# FE3_V3_REV10c.net
KiCad netlist of a schematic drawn in EAGLE
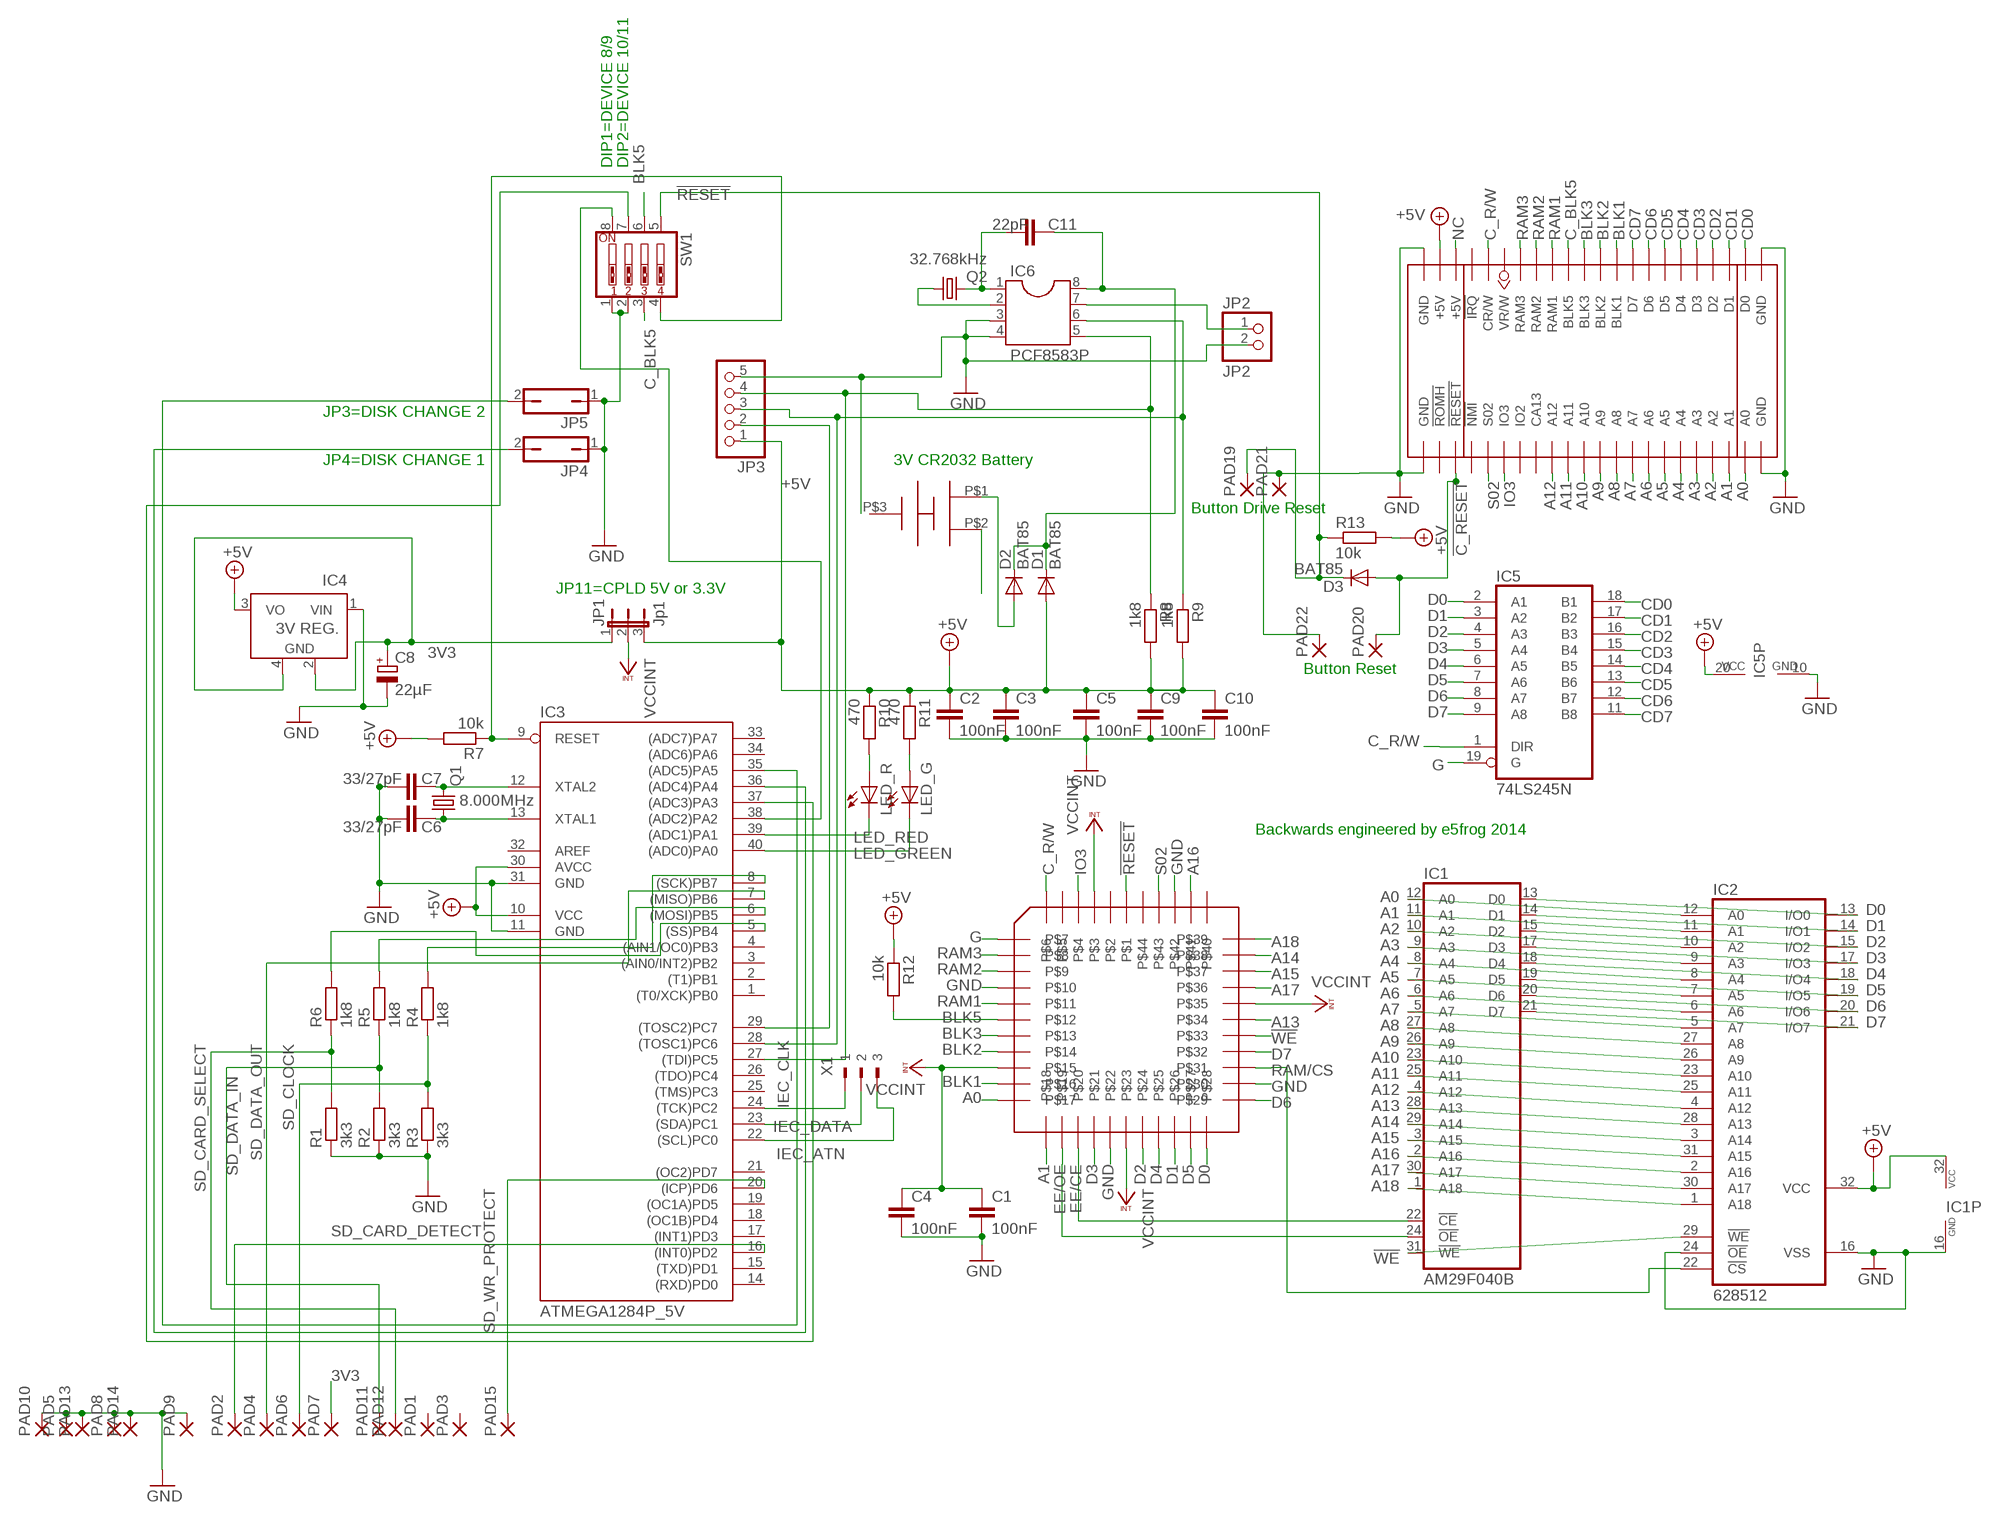
[diagram p0: schematic, sheet 1]

(export (version "E")
  (design (tool "Eeschema 10.0.6"))
  (components
    (comp (ref "C1")
      (value "100nF")
      (footprint "eagle-import:C050-025X075")
      (libsource (lib "eagle-import") (part "C-EU050-025X075"))
    )
    (comp (ref "C2")
      (value "100nF")
      (footprint "eagle-import:C050-025X075")
      (libsource (lib "eagle-import") (part "C-EU050-025X075"))
    )
    (comp (ref "C3")
      (value "100nF")
      (footprint "eagle-import:C050-025X075")
      (libsource (lib "eagle-import") (part "C-EU050-025X075"))
    )
    (comp (ref "C4")
      (value "100nF")
      (footprint "eagle-import:C050-025X075")
      (libsource (lib "eagle-import") (part "C-EU050-025X075"))
    )
    (comp (ref "C5")
      (value "100nF")
      (footprint "eagle-import:C050-025X075")
      (libsource (lib "eagle-import") (part "C-EU050-025X075"))
    )
    (comp (ref "C6")
      (value "33/27pF")
      (footprint "eagle-import:C025-024X044")
      (libsource (lib "eagle-import") (part "C-EU025-024X044"))
    )
    (comp (ref "C7")
      (value "33/27pF")
      (footprint "eagle-import:C025-024X044")
      (libsource (lib "eagle-import") (part "C-EU025-024X044"))
    )
    (comp (ref "C8")
      (value "22µF")
      (footprint "eagle-import:E2-4")
      (libsource (lib "eagle-import") (part "CPOL-EUE2-4"))
    )
    (comp (ref "C9")
      (value "100nF")
      (footprint "eagle-import:C050-025X075")
      (libsource (lib "eagle-import") (part "C-EU050-025X075"))
    )
    (comp (ref "C10")
      (value "100nF")
      (footprint "eagle-import:C050-025X075")
      (libsource (lib "eagle-import") (part "C-EU050-025X075"))
    )
    (comp (ref "C11")
      (value "22pF")
      (footprint "eagle-import:C5B2.5")
      (libsource (lib "eagle-import") (part "C5/2.5"))
    )
    (comp (ref "D1")
      (value "BAT85")
      (footprint "eagle-import:DO34-7")
      (libsource (lib "eagle-import") (part "BAT81"))
    )
    (comp (ref "D2")
      (value "BAT85")
      (footprint "eagle-import:DO34-7")
      (libsource (lib "eagle-import") (part "BAT81"))
    )
    (comp (ref "D3")
      (value "BAT85")
      (footprint "eagle-import:DO34-7")
      (libsource (lib "eagle-import") (part "BAT81"))
    )
    (comp (ref "IC1")
      (value "AM29F040B")
      (footprint "eagle-import:DIL32")
      (libsource (lib "eagle-import") (part "AM29F040PAM29F040B"))
    )
    (comp (ref "IC2")
      (value "628512")
      (footprint "eagle-import:DIL32")
      (libsource (lib "eagle-import") (part "628512P"))
    )
    (comp (ref "IC3")
      (value "ATMEGA1284P_5V")
      (footprint "eagle-import:DIL40")
      (fields (field (name "MPN") "ATMEGA32-16PU"))
      (libsource (lib "eagle-import") (part "MEGA32-P"))
    )
    (comp (ref "IC4")
      (value "3V REG.")
      (footprint "eagle-import:SOT223")
      (fields (field (name "MF") "NATIONAL SEMICONDUCTOR") (field (name "MPN") "LM2936MP-3.0/NOPB"))
      (libsource (lib "eagle-import") (part "LM2936MP?-3.0"))
    )
    (comp (ref "IC5")
      (value "74LS245N")
      (footprint "eagle-import:DIL20")
      (libsource (lib "eagle-import") (part "74245NLS"))
    )
    (comp (ref "IC6")
      (value "PCF8583P")
      (footprint "eagle-import:DIL08")
      (libsource (lib "eagle-import") (part "DIL8"))
    )
    (comp (ref "JP1")
      (value "Jp1")
      (footprint "eagle-import:JP2_N")
      (libsource (lib "eagle-import") (part "JP2E_N"))
    )
    (comp (ref "JP2")
      (value "JP2")
      (footprint "eagle-import:1X02")
      (libsource (lib "eagle-import") (part "PINHD-1X2"))
    )
    (comp (ref "JP3")
      (value "PINHD-1X5")
      (footprint "eagle-import:1X05")
      (libsource (lib "eagle-import") (part "PINHD-1X5"))
    )
    (comp (ref "JP4")
      (value "JP1Q")
      (footprint "eagle-import:JP1")
      (libsource (lib "eagle-import") (part "JP1Q"))
    )
    (comp (ref "JP5")
      (value "JP1Q")
      (footprint "eagle-import:JP1")
      (libsource (lib "eagle-import") (part "JP1Q"))
    )
    (comp (ref "LED_G")
      (value "LED3MM")
      (footprint "eagle-import:LED3MM")
      (libsource (lib "eagle-import") (part "LED3MM"))
    )
    (comp (ref "LED_R")
      (value "LED3MM")
      (footprint "eagle-import:LED3MM")
      (libsource (lib "eagle-import") (part "LED3MM"))
    )
    (comp (ref "PAD1")
      (value "SMD_EZ1")
      (footprint "eagle-import:SMD0,7-254")
      (libsource (lib "eagle-import") (part "SMD_EZ1"))
    )
    (comp (ref "PAD2")
      (value "SMD_EZ1")
      (footprint "eagle-import:SMD0,7-254")
      (libsource (lib "eagle-import") (part "SMD_EZ1"))
    )
    (comp (ref "PAD3")
      (value "SMD2")
      (footprint "eagle-import:SMD1,27-2,54")
      (libsource (lib "eagle-import") (part "SMD2"))
    )
    (comp (ref "PAD4")
      (value "SMD2")
      (footprint "eagle-import:SMD1,27-2,54")
      (libsource (lib "eagle-import") (part "SMD2"))
    )
    (comp (ref "PAD5")
      (value "SMD2")
      (footprint "eagle-import:SMD1,27-2,54")
      (libsource (lib "eagle-import") (part "SMD2"))
    )
    (comp (ref "PAD6")
      (value "SMD2")
      (footprint "eagle-import:SMD1,27-2,54")
      (libsource (lib "eagle-import") (part "SMD2"))
    )
    (comp (ref "PAD7")
      (value "SMD2")
      (footprint "eagle-import:SMD1,27-2,54")
      (libsource (lib "eagle-import") (part "SMD2"))
    )
    (comp (ref "PAD8")
      (value "SMD2")
      (footprint "eagle-import:SMD1,27-2,54")
      (libsource (lib "eagle-import") (part "SMD2"))
    )
    (comp (ref "PAD9")
      (value "SMD2")
      (footprint "eagle-import:SMD1,27-2,54")
      (libsource (lib "eagle-import") (part "SMD2"))
    )
    (comp (ref "PAD10")
      (value "SMD2")
      (footprint "eagle-import:SMD1,27-2,54")
      (libsource (lib "eagle-import") (part "SMD2"))
    )
    (comp (ref "PAD11")
      (value "SMD2")
      (footprint "eagle-import:SMD1,27-2,54")
      (libsource (lib "eagle-import") (part "SMD2"))
    )
    (comp (ref "PAD12")
      (value "SMD2")
      (footprint "eagle-import:SMD1,27-2,54")
      (libsource (lib "eagle-import") (part "SMD2"))
    )
    (comp (ref "PAD13")
      (value "SMD2")
      (footprint "eagle-import:SMD1,27-2,54")
      (libsource (lib "eagle-import") (part "SMD2"))
    )
    (comp (ref "PAD14")
      (value "SMD2")
      (footprint "eagle-import:SMD1,27-2,54")
      (libsource (lib "eagle-import") (part "SMD2"))
    )
    (comp (ref "PAD15")
      (value "SMD_EZ1")
      (footprint "eagle-import:SMD0,7-254")
      (libsource (lib "eagle-import") (part "SMD_EZ1"))
    )
    (comp (ref "PAD19")
      (value "SMD5")
      (footprint "eagle-import:SMD2,54-5,08")
      (libsource (lib "eagle-import") (part "SMD5"))
    )
    (comp (ref "PAD20")
      (value "SMD5")
      (footprint "eagle-import:SMD2,54-5,08")
      (libsource (lib "eagle-import") (part "SMD5"))
    )
    (comp (ref "PAD21")
      (value "SMD5")
      (footprint "eagle-import:SMD2,54-5,08")
      (libsource (lib "eagle-import") (part "SMD5"))
    )
    (comp (ref "PAD22")
      (value "SMD5")
      (footprint "eagle-import:SMD2,54-5,08")
      (libsource (lib "eagle-import") (part "SMD5"))
    )
    (comp (ref "Q1")
      (value "8.000MHz")
      (footprint "eagle-import:HC49U-V")
      (libsource (lib "eagle-import") (part "CRYSTALHC49U-V"))
    )
    (comp (ref "Q2")
      (value "32.768kHz")
      (footprint "eagle-import:TC26H")
      (libsource (lib "eagle-import") (part "CRYSTALTC26H"))
    )
    (comp (ref "R1")
      (value "3k3")
      (footprint "eagle-import:0207_10")
      (libsource (lib "eagle-import") (part "R-EU_0207/10"))
    )
    (comp (ref "R2")
      (value "3k3")
      (footprint "eagle-import:0207_10")
      (libsource (lib "eagle-import") (part "R-EU_0207/10"))
    )
    (comp (ref "R3")
      (value "3k3")
      (footprint "eagle-import:0207_10")
      (libsource (lib "eagle-import") (part "R-EU_0207/10"))
    )
    (comp (ref "R4")
      (value "1k8")
      (footprint "eagle-import:0207_10")
      (libsource (lib "eagle-import") (part "R-EU_0207/10"))
    )
    (comp (ref "R5")
      (value "1k8")
      (footprint "eagle-import:0207_10")
      (libsource (lib "eagle-import") (part "R-EU_0207/10"))
    )
    (comp (ref "R6")
      (value "1k8")
      (footprint "eagle-import:0207_10")
      (libsource (lib "eagle-import") (part "R-EU_0207/10"))
    )
    (comp (ref "R7")
      (value "10k")
      (footprint "eagle-import:0207_10")
      (libsource (lib "eagle-import") (part "R-EU_0207/10"))
    )
    (comp (ref "R8")
      (value "1k8")
      (footprint "eagle-import:0207_10")
      (libsource (lib "eagle-import") (part "R-EU_0207/10"))
    )
    (comp (ref "R9")
      (value "1k8")
      (footprint "eagle-import:0207_10")
      (libsource (lib "eagle-import") (part "R-EU_0207/10"))
    )
    (comp (ref "R10")
      (value "470")
      (footprint "eagle-import:0207_10")
      (libsource (lib "eagle-import") (part "R-EU_0207/10"))
    )
    (comp (ref "R11")
      (value "470")
      (footprint "eagle-import:0207_10")
      (libsource (lib "eagle-import") (part "R-EU_0207/10"))
    )
    (comp (ref "R12")
      (value "10k")
      (footprint "eagle-import:0207_10")
      (libsource (lib "eagle-import") (part "R-EU_0207/10"))
    )
    (comp (ref "R13")
      (value "10k")
      (footprint "eagle-import:0207_10")
      (libsource (lib "eagle-import") (part "R-EU_0207/10"))
    )
    (comp (ref "SW1")
      (value "SW_DIP-4")
      (footprint "eagle-import:EDG-04")
      (libsource (lib "eagle-import") (part "SW_DIP-4"))
    )
    (comp (ref "U$1")
      (value "CPLD-ATF1504-AS")
      (footprint "eagle-import:S44")
      (libsource (lib "eagle-import") (part "CPLD-ATF1504-AS"))
    )
    (comp (ref "U$2")
      (value "VIC-20_EXPANSION")
      (footprint "eagle-import:VIC-20_EXPANSION")
      (libsource (lib "eagle-import") (part "VIC-20_EXPANSION"))
    )
    (comp (ref "U$3")
      (value "CR2032_RETAINER_PK5")
      (footprint "eagle-import:CR2032_RETAINER_PK5")
      (libsource (lib "eagle-import") (part "CR2032_RETAINER_PK5"))
    )
    (comp (ref "X1")
      (value "90-3")
      (footprint "eagle-import:90-3")
      (libsource (lib "eagle-import") (part "90-3"))
    )
  )
  (nets
    (net (code "1") (name "+5V") (class "Default")
      (node (ref "C10") (pin "1") (pinfunction "1_1") (pintype "passive"))
      (node (ref "C2") (pin "1") (pinfunction "1_1") (pintype "passive"))
      (node (ref "C3") (pin "1") (pinfunction "1_1") (pintype "passive"))
      (node (ref "C5") (pin "1") (pinfunction "1_1") (pintype "passive"))
      (node (ref "C9") (pin "1") (pinfunction "1_1") (pintype "passive"))
      (node (ref "D1") (pin "A") (pinfunction "A_A") (pintype "passive"))
      (node (ref "IC1") (pin "32") (pinfunction "VCC_32") (pintype "power_in"))
      (node (ref "IC2") (pin "32") (pinfunction "VCC_32") (pintype "power_in"))
      (node (ref "IC3") (pin "10") (pinfunction "VCC_10") (pintype "power_in"))
      (node (ref "IC3") (pin "30") (pinfunction "AVCC_30") (pintype "power_in"))
      (node (ref "IC4") (pin "3") (pinfunction "VO_3") (pintype "passive"))
      (node (ref "IC5") (pin "20") (pinfunction "VCC_20") (pintype "power_in"))
      (node (ref "JP1") (pin "3") (pinfunction "3_3") (pintype "passive"))
      (node (ref "JP3") (pin "1") (pinfunction "1_1") (pintype "passive"))
      (node (ref "R10") (pin "1") (pinfunction "1_1") (pintype "passive"))
      (node (ref "R11") (pin "1") (pinfunction "1_1") (pintype "passive"))
      (node (ref "R12") (pin "1") (pinfunction "1_1") (pintype "passive"))
      (node (ref "R13") (pin "2") (pinfunction "2_2") (pintype "passive"))
      (node (ref "R7") (pin "2") (pinfunction "2_2") (pintype "passive"))
      (node (ref "R8") (pin "2") (pinfunction "2_2") (pintype "passive"))
      (node (ref "R9") (pin "2") (pinfunction "2_2") (pintype "passive"))
      (node (ref "U$2") (pin "P$2") (pinfunction "+5V_P$2") (pintype "power_in"))
    )
    (net (code "2") (name "/3V3") (class "Default")
      (node (ref "C8") (pin "+") (pinfunction "+_+") (pintype "passive"))
      (node (ref "IC4") (pin "2") (pinfunction "GND_2") (pintype "passive"))
      (node (ref "IC4") (pin "4") (pinfunction "GND_4") (pintype "passive"))
      (node (ref "JP1") (pin "1") (pinfunction "1_1") (pintype "passive"))
      (node (ref "PAD7") (pin "1") (pinfunction "P_1") (pintype "passive"))
    )
    (net (code "3") (name "/A0") (class "Default")
      (node (ref "IC1") (pin "12") (pinfunction "A0_12") (pintype "input"))
      (node (ref "IC2") (pin "12") (pinfunction "A0_12") (pintype "input"))
      (node (ref "U$1") (pin "17") (pinfunction "P$17_17") (pintype "bidirectional"))
      (node (ref "U$2") (pin "P$43") (pinfunction "A0_P$43") (pintype "bidirectional"))
    )
    (net (code "4") (name "/A1") (class "Default")
      (node (ref "IC1") (pin "11") (pinfunction "A1_11") (pintype "input"))
      (node (ref "IC2") (pin "11") (pinfunction "A1_11") (pintype "input"))
      (node (ref "U$1") (pin "18") (pinfunction "P$18_18") (pintype "bidirectional"))
      (node (ref "U$2") (pin "P$42") (pinfunction "A1_P$42") (pintype "bidirectional"))
    )
    (net (code "5") (name "/A2") (class "Default")
      (node (ref "IC1") (pin "10") (pinfunction "A2_10") (pintype "input"))
      (node (ref "IC2") (pin "10") (pinfunction "A2_10") (pintype "input"))
      (node (ref "U$2") (pin "P$41") (pinfunction "A2_P$41") (pintype "bidirectional"))
    )
    (net (code "6") (name "/A3") (class "Default")
      (node (ref "IC1") (pin "9") (pinfunction "A3_9") (pintype "input"))
      (node (ref "IC2") (pin "9") (pinfunction "A3_9") (pintype "input"))
      (node (ref "U$2") (pin "P$40") (pinfunction "A3_P$40") (pintype "bidirectional"))
    )
    (net (code "7") (name "/A4") (class "Default")
      (node (ref "IC1") (pin "8") (pinfunction "A4_8") (pintype "input"))
      (node (ref "IC2") (pin "8") (pinfunction "A4_8") (pintype "input"))
      (node (ref "U$2") (pin "P$39") (pinfunction "A4_P$39") (pintype "bidirectional"))
    )
    (net (code "8") (name "/A5") (class "Default")
      (node (ref "IC1") (pin "7") (pinfunction "A5_7") (pintype "input"))
      (node (ref "IC2") (pin "7") (pinfunction "A5_7") (pintype "input"))
      (node (ref "U$2") (pin "P$38") (pinfunction "A5_P$38") (pintype "bidirectional"))
    )
    (net (code "9") (name "/A6") (class "Default")
      (node (ref "IC1") (pin "6") (pinfunction "A6_6") (pintype "input"))
      (node (ref "IC2") (pin "6") (pinfunction "A6_6") (pintype "input"))
      (node (ref "U$2") (pin "P$37") (pinfunction "A6_P$37") (pintype "bidirectional"))
    )
    (net (code "10") (name "/A7") (class "Default")
      (node (ref "IC1") (pin "5") (pinfunction "A7_5") (pintype "input"))
      (node (ref "IC2") (pin "5") (pinfunction "A7_5") (pintype "input"))
      (node (ref "U$2") (pin "P$36") (pinfunction "A7_P$36") (pintype "bidirectional"))
    )
    (net (code "11") (name "/A8") (class "Default")
      (node (ref "IC1") (pin "27") (pinfunction "A8_27") (pintype "input"))
      (node (ref "IC2") (pin "27") (pinfunction "A8_27") (pintype "input"))
      (node (ref "U$2") (pin "P$35") (pinfunction "A8_P$35") (pintype "bidirectional"))
    )
    (net (code "12") (name "/A9") (class "Default")
      (node (ref "IC1") (pin "26") (pinfunction "A9_26") (pintype "input"))
      (node (ref "IC2") (pin "26") (pinfunction "A9_26") (pintype "input"))
      (node (ref "U$2") (pin "P$34") (pinfunction "A9_P$34") (pintype "bidirectional"))
    )
    (net (code "13") (name "/A10") (class "Default")
      (node (ref "IC1") (pin "23") (pinfunction "A10_23") (pintype "input"))
      (node (ref "IC2") (pin "23") (pinfunction "A10_23") (pintype "input"))
      (node (ref "U$2") (pin "P$33") (pinfunction "A10_P$33") (pintype "bidirectional"))
    )
    (net (code "14") (name "/A11") (class "Default")
      (node (ref "IC1") (pin "25") (pinfunction "A11_25") (pintype "input"))
      (node (ref "IC2") (pin "25") (pinfunction "A11_25") (pintype "input"))
      (node (ref "U$2") (pin "P$32") (pinfunction "A11_P$32") (pintype "bidirectional"))
    )
    (net (code "15") (name "/A12") (class "Default")
      (node (ref "IC1") (pin "4") (pinfunction "A12_4") (pintype "input"))
      (node (ref "IC2") (pin "4") (pinfunction "A12_4") (pintype "input"))
      (node (ref "U$2") (pin "P$31") (pinfunction "A12_P$31") (pintype "bidirectional"))
    )
    (net (code "16") (name "/A13") (class "Default")
      (node (ref "IC1") (pin "28") (pinfunction "A13_28") (pintype "input"))
      (node (ref "IC2") (pin "28") (pinfunction "A13_28") (pintype "input"))
      (node (ref "U$1") (pin "34") (pinfunction "P$34_34") (pintype "bidirectional"))
    )
    (net (code "17") (name "/A14") (class "Default")
      (node (ref "IC1") (pin "29") (pinfunction "A14_29") (pintype "input"))
      (node (ref "IC2") (pin "3") (pinfunction "A14_3") (pintype "input"))
      (node (ref "U$1") (pin "38") (pinfunction "P$38_38") (pintype "bidirectional"))
    )
    (net (code "18") (name "/A15") (class "Default")
      (node (ref "IC1") (pin "3") (pinfunction "A15_3") (pintype "input"))
      (node (ref "IC2") (pin "31") (pinfunction "A15_31") (pintype "input"))
      (node (ref "U$1") (pin "37") (pinfunction "P$37_37") (pintype "bidirectional"))
    )
    (net (code "19") (name "/A16") (class "Default")
      (node (ref "IC1") (pin "2") (pinfunction "A16_2") (pintype "input"))
      (node (ref "IC2") (pin "2") (pinfunction "A16_2") (pintype "input"))
      (node (ref "U$1") (pin "41") (pinfunction "P$41_41") (pintype "bidirectional"))
    )
    (net (code "20") (name "/A17") (class "Default")
      (node (ref "IC1") (pin "30") (pinfunction "A17_30") (pintype "input"))
      (node (ref "IC2") (pin "30") (pinfunction "A17_30") (pintype "input"))
      (node (ref "U$1") (pin "36") (pinfunction "P$36_36") (pintype "bidirectional"))
    )
    (net (code "21") (name "/A18") (class "Default")
      (node (ref "IC1") (pin "1") (pinfunction "A18_1") (pintype "input"))
      (node (ref "IC2") (pin "1") (pinfunction "A18_1") (pintype "input"))
      (node (ref "U$1") (pin "39") (pinfunction "P$39_39") (pintype "bidirectional"))
    )
    (net (code "22") (name "/BLK1") (class "Default")
      (node (ref "U$1") (pin "16") (pinfunction "P$16_16") (pintype "bidirectional"))
      (node (ref "U$2") (pin "P$13") (pinfunction "BLK1_P$13") (pintype "bidirectional"))
    )
    (net (code "23") (name "/BLK2") (class "Default")
      (node (ref "U$1") (pin "14") (pinfunction "P$14_14") (pintype "bidirectional"))
      (node (ref "U$2") (pin "P$12") (pinfunction "BLK2_P$12") (pintype "bidirectional"))
    )
    (net (code "24") (name "/BLK3") (class "Default")
      (node (ref "U$1") (pin "13") (pinfunction "P$13_13") (pintype "bidirectional"))
      (node (ref "U$2") (pin "P$11") (pinfunction "BLK3_P$11") (pintype "bidirectional"))
    )
    (net (code "25") (name "/BLK5") (class "Default")
      (node (ref "R12") (pin "2") (pinfunction "2_2") (pintype "passive"))
      (node (ref "SW1") (pin "6") (pinfunction "6_6") (pintype "passive"))
      (node (ref "U$1") (pin "12") (pinfunction "P$12_12") (pintype "bidirectional"))
    )
    (net (code "26") (name "/CD0") (class "Default")
      (node (ref "IC5") (pin "18") (pinfunction "B1_18") (pintype "bidirectional"))
      (node (ref "U$2") (pin "P$21") (pinfunction "D0_P$21") (pintype "bidirectional"))
    )
    (net (code "27") (name "/CD1") (class "Default")
      (node (ref "IC5") (pin "17") (pinfunction "B2_17") (pintype "bidirectional"))
      (node (ref "U$2") (pin "P$20") (pinfunction "D1_P$20") (pintype "bidirectional"))
    )
    (net (code "28") (name "/CD2") (class "Default")
      (node (ref "IC5") (pin "16") (pinfunction "B3_16") (pintype "bidirectional"))
      (node (ref "U$2") (pin "P$19") (pinfunction "D2_P$19") (pintype "bidirectional"))
    )
    (net (code "29") (name "/CD3") (class "Default")
      (node (ref "IC5") (pin "15") (pinfunction "B4_15") (pintype "bidirectional"))
      (node (ref "U$2") (pin "P$18") (pinfunction "D3_P$18") (pintype "bidirectional"))
    )
    (net (code "30") (name "/CD4") (class "Default")
      (node (ref "IC5") (pin "14") (pinfunction "B5_14") (pintype "bidirectional"))
      (node (ref "U$2") (pin "P$17") (pinfunction "D4_P$17") (pintype "bidirectional"))
    )
    (net (code "31") (name "/CD5") (class "Default")
      (node (ref "IC5") (pin "13") (pinfunction "B6_13") (pintype "bidirectional"))
      (node (ref "U$2") (pin "P$16") (pinfunction "D5_P$16") (pintype "bidirectional"))
    )
    (net (code "32") (name "/CD6") (class "Default")
      (node (ref "IC5") (pin "12") (pinfunction "B7_12") (pintype "bidirectional"))
      (node (ref "U$2") (pin "P$15") (pinfunction "D6_P$15") (pintype "bidirectional"))
    )
    (net (code "33") (name "/CD7") (class "Default")
      (node (ref "IC5") (pin "11") (pinfunction "B8_11") (pintype "bidirectional"))
      (node (ref "U$2") (pin "P$14") (pinfunction "D7_P$14") (pintype "bidirectional"))
    )
    (net (code "34") (name "/C_BLK5") (class "Default")
      (node (ref "SW1") (pin "3") (pinfunction "3_3") (pintype "passive"))
      (node (ref "U$2") (pin "P$10") (pinfunction "BLK5_P$10") (pintype "bidirectional"))
    )
    (net (code "35") (name "/C_R{slash}W") (class "Default")
      (node (ref "IC5") (pin "1") (pinfunction "DIR_1") (pintype "input"))
      (node (ref "U$1") (pin "6") (pinfunction "P$6_6") (pintype "bidirectional"))
      (node (ref "U$2") (pin "P$5") (pinfunction "CR/W_P$5") (pintype "bidirectional"))
    )
    (net (code "36") (name "/D0") (class "Default")
      (node (ref "IC1") (pin "13") (pinfunction "D0_13") (pintype "tri_state"))
      (node (ref "IC2") (pin "13") (pinfunction "I/O0_13") (pintype "bidirectional"))
      (node (ref "IC5") (pin "2") (pinfunction "A1_2") (pintype "bidirectional"))
      (node (ref "U$1") (pin "28") (pinfunction "P$28_28") (pintype "bidirectional"))
    )
    (net (code "37") (name "/D1") (class "Default")
      (node (ref "IC1") (pin "14") (pinfunction "D1_14") (pintype "tri_state"))
      (node (ref "IC2") (pin "14") (pinfunction "I/O1_14") (pintype "bidirectional"))
      (node (ref "IC5") (pin "3") (pinfunction "A2_3") (pintype "bidirectional"))
      (node (ref "U$1") (pin "26") (pinfunction "P$26_26") (pintype "bidirectional"))
    )
    (net (code "38") (name "/D2") (class "Default")
      (node (ref "IC1") (pin "15") (pinfunction "D2_15") (pintype "tri_state"))
      (node (ref "IC2") (pin "15") (pinfunction "I/O2_15") (pintype "bidirectional"))
      (node (ref "IC5") (pin "4") (pinfunction "A3_4") (pintype "bidirectional"))
      (node (ref "U$1") (pin "24") (pinfunction "P$24_24") (pintype "bidirectional"))
    )
    (net (code "39") (name "/D3") (class "Default")
      (node (ref "IC1") (pin "17") (pinfunction "D3_17") (pintype "tri_state"))
      (node (ref "IC2") (pin "17") (pinfunction "I/O3_17") (pintype "bidirectional"))
      (node (ref "IC5") (pin "5") (pinfunction "A4_5") (pintype "bidirectional"))
      (node (ref "U$1") (pin "21") (pinfunction "P$21_21") (pintype "bidirectional"))
    )
    (net (code "40") (name "/D4") (class "Default")
      (node (ref "IC1") (pin "18") (pinfunction "D4_18") (pintype "tri_state"))
      (node (ref "IC2") (pin "18") (pinfunction "I/O4_18") (pintype "bidirectional"))
      (node (ref "IC5") (pin "6") (pinfunction "A5_6") (pintype "bidirectional"))
      (node (ref "U$1") (pin "25") (pinfunction "P$25_25") (pintype "bidirectional"))
    )
    (net (code "41") (name "/D5") (class "Default")
      (node (ref "IC1") (pin "19") (pinfunction "D5_19") (pintype "tri_state"))
      (node (ref "IC2") (pin "19") (pinfunction "I/O5_19") (pintype "bidirectional"))
      (node (ref "IC5") (pin "7") (pinfunction "A6_7") (pintype "bidirectional"))
      (node (ref "U$1") (pin "27") (pinfunction "P$27_27") (pintype "bidirectional"))
    )
    (net (code "42") (name "/D6") (class "Default")
      (node (ref "IC1") (pin "20") (pinfunction "D6_20") (pintype "tri_state"))
      (node (ref "IC2") (pin "20") (pinfunction "I/O6_20") (pintype "bidirectional"))
      (node (ref "IC5") (pin "8") (pinfunction "A7_8") (pintype "bidirectional"))
      (node (ref "U$1") (pin "29") (pinfunction "P$29_29") (pintype "bidirectional"))
    )
    (net (code "43") (name "/D7") (class "Default")
      (node (ref "IC1") (pin "21") (pinfunction "D7_21") (pintype "tri_state"))
      (node (ref "IC2") (pin "21") (pinfunction "I/O7_21") (pintype "bidirectional"))
      (node (ref "IC5") (pin "9") (pinfunction "A8_9") (pintype "bidirectional"))
      (node (ref "U$1") (pin "32") (pinfunction "P$32_32") (pintype "bidirectional"))
    )
    (net (code "44") (name "/EE{slash}CE") (class "Default")
      (node (ref "IC1") (pin "22") (pinfunction "~{CE}_22") (pintype "input"))
      (node (ref "U$1") (pin "20") (pinfunction "P$20_20") (pintype "bidirectional"))
    )
    (net (code "45") (name "/EE{slash}OE") (class "Default")
      (node (ref "IC1") (pin "24") (pinfunction "~{OE}_24") (pintype "input"))
      (node (ref "U$1") (pin "19") (pinfunction "P$19_19") (pintype "bidirectional"))
    )
    (net (code "46") (name "/G") (class "Default")
      (node (ref "IC5") (pin "19") (pinfunction "G_19") (pintype "input"))
      (node (ref "U$1") (pin "7") (pinfunction "P$7_7") (pintype "bidirectional"))
    )
    (net (code "47") (name "/IEC_ATN") (class "Default")
      (node (ref "IC3") (pin "22") (pinfunction "(SCL)PC0_22") (pintype "bidirectional"))
      (node (ref "X1") (pin "3") (pinfunction "3_3") (pintype "passive"))
    )
    (net (code "48") (name "/IEC_CLK") (class "Default")
      (node (ref "IC3") (pin "24") (pinfunction "(TCK)PC2_24") (pintype "bidirectional"))
      (node (ref "X1") (pin "1") (pinfunction "1_1") (pintype "passive"))
    )
    (net (code "49") (name "/IEC_DATA") (class "Default")
      (node (ref "IC3") (pin "23") (pinfunction "(SDA)PC1_23") (pintype "bidirectional"))
      (node (ref "X1") (pin "2") (pinfunction "2_2") (pintype "passive"))
    )
    (net (code "50") (name "/IO3") (class "Default")
      (node (ref "U$1") (pin "4") (pinfunction "P$4_4") (pintype "bidirectional"))
      (node (ref "U$2") (pin "P$28") (pinfunction "IO3_P$28") (pintype "bidirectional"))
    )
    (net (code "51") (name "/LED_GREEN") (class "Default")
      (node (ref "IC3") (pin "40") (pinfunction "(ADC0)PA0_40") (pintype "bidirectional"))
      (node (ref "LED_G") (pin "K") (pinfunction "C_K") (pintype "passive"))
    )
    (net (code "52") (name "/LED_RED") (class "Default")
      (node (ref "IC3") (pin "39") (pinfunction "(ADC1)PA1_39") (pintype "bidirectional"))
      (node (ref "LED_R") (pin "K") (pinfunction "C_K") (pintype "passive"))
    )
    (net (code "53") (name "/NC") (class "Default")
      (node (ref "U$2") (pin "P$3") (pinfunction "+5V_P$3") (pintype "power_in"))
    )
    (net (code "54") (name "/P$3") (class "Default")
      (node (ref "U$3") (pin "P$3") (pinfunction "P$3_P$3") (pintype "power_in"))
    )
    (net (code "55") (name "/RAM1") (class "Default")
      (node (ref "U$1") (pin "11") (pinfunction "P$11_11") (pintype "bidirectional"))
      (node (ref "U$2") (pin "P$9") (pinfunction "RAM1_P$9") (pintype "bidirectional"))
    )
    (net (code "56") (name "/RAM2") (class "Default")
      (node (ref "U$1") (pin "9") (pinfunction "P$9_9") (pintype "bidirectional"))
      (node (ref "U$2") (pin "P$8") (pinfunction "RAM2_P$8") (pintype "bidirectional"))
    )
    (net (code "57") (name "/RAM3") (class "Default")
      (node (ref "U$1") (pin "8") (pinfunction "P$8_8") (pintype "bidirectional"))
      (node (ref "U$2") (pin "P$7") (pinfunction "RAM3_P$7") (pintype "bidirectional"))
    )
    (net (code "58") (name "/RAM{slash}CS") (class "Default")
      (node (ref "IC2") (pin "22") (pinfunction "~{CS}_22") (pintype "input"))
      (node (ref "U$1") (pin "31") (pinfunction "P$31_31") (pintype "bidirectional"))
    )
    (net (code "59") (name "/S02") (class "Default")
      (node (ref "U$1") (pin "43") (pinfunction "P$43_43") (pintype "bidirectional"))
      (node (ref "U$2") (pin "P$27") (pinfunction "S02_P$27") (pintype "bidirectional"))
    )
    (net (code "60") (name "/SD_CARD_DETECT") (class "Default")
      (node (ref "IC3") (pin "16") (pinfunction "(INT0)PD2_16") (pintype "bidirectional"))
      (node (ref "PAD2") (pin "1") (pinfunction "P_1") (pintype "passive"))
    )
    (net (code "61") (name "/SD_CARD_SELECT") (class "Default")
      (node (ref "PAD12") (pin "1") (pinfunction "P_1") (pintype "passive"))
      (node (ref "R1") (pin "2") (pinfunction "2_2") (pintype "passive"))
      (node (ref "R6") (pin "1") (pinfunction "1_1") (pintype "passive"))
    )
    (net (code "62") (name "/SD_CLOCK") (class "Default")
      (node (ref "PAD6") (pin "1") (pinfunction "P_1") (pintype "passive"))
      (node (ref "R3") (pin "2") (pinfunction "2_2") (pintype "passive"))
      (node (ref "R4") (pin "1") (pinfunction "1_1") (pintype "passive"))
    )
    (net (code "63") (name "/SD_DATA_IN") (class "Default")
      (node (ref "PAD11") (pin "1") (pinfunction "P_1") (pintype "passive"))
      (node (ref "R2") (pin "2") (pinfunction "2_2") (pintype "passive"))
      (node (ref "R5") (pin "1") (pinfunction "1_1") (pintype "passive"))
    )
    (net (code "64") (name "/SD_DATA_OUT") (class "Default")
      (node (ref "IC3") (pin "7") (pinfunction "(MISO)PB6_7") (pintype "bidirectional"))
      (node (ref "PAD4") (pin "1") (pinfunction "P_1") (pintype "passive"))
    )
    (net (code "65") (name "/SD_WR_PROTECT") (class "Default")
      (node (ref "IC3") (pin "20") (pinfunction "(ICP)PD6_20") (pintype "bidirectional"))
      (node (ref "PAD15") (pin "1") (pinfunction "P_1") (pintype "passive"))
    )
    (net (code "66") (name "/~{C_RESET}") (class "Default")
      (node (ref "D3") (pin "A") (pinfunction "A_A") (pintype "passive"))
      (node (ref "PAD20") (pin "1") (pinfunction "P_1") (pintype "passive"))
      (node (ref "U$2") (pin "P$25") (pinfunction "~{RESET}_P$25") (pintype "bidirectional"))
    )
    (net (code "67") (name "/~{RESET}") (class "Default")
      (node (ref "D3") (pin "C") (pinfunction "C_C") (pintype "passive"))
      (node (ref "PAD19") (pin "1") (pinfunction "P_1") (pintype "passive"))
      (node (ref "R13") (pin "1") (pinfunction "1_1") (pintype "passive"))
      (node (ref "SW1") (pin "5") (pinfunction "5_5") (pintype "passive"))
      (node (ref "U$1") (pin "1") (pinfunction "P$1_1") (pintype "bidirectional"))
    )
    (net (code "68") (name "/~{WE}") (class "Default")
      (node (ref "IC1") (pin "31") (pinfunction "~{WE}_31") (pintype "input"))
      (node (ref "IC2") (pin "29") (pinfunction "~{WE}_29") (pintype "input"))
      (node (ref "U$1") (pin "33") (pinfunction "P$33_33") (pintype "bidirectional"))
    )
    (net (code "69") (name "GND") (class "Default")
      (node (ref "C1") (pin "2") (pinfunction "2_2") (pintype "passive"))
      (node (ref "C10") (pin "2") (pinfunction "2_2") (pintype "passive"))
      (node (ref "C2") (pin "2") (pinfunction "2_2") (pintype "passive"))
      (node (ref "C3") (pin "2") (pinfunction "2_2") (pintype "passive"))
      (node (ref "C4") (pin "2") (pinfunction "2_2") (pintype "passive"))
      (node (ref "C5") (pin "2") (pinfunction "2_2") (pintype "passive"))
      (node (ref "C6") (pin "2") (pinfunction "2_2") (pintype "passive"))
      (node (ref "C7") (pin "2") (pinfunction "2_2") (pintype "passive"))
      (node (ref "C8") (pin "-") (pinfunction "-_-") (pintype "passive"))
      (node (ref "C9") (pin "2") (pinfunction "2_2") (pintype "passive"))
      (node (ref "IC1") (pin "16") (pinfunction "GND_16") (pintype "power_in"))
      (node (ref "IC2") (pin "16") (pinfunction "VSS_16") (pintype "power_in"))
      (node (ref "IC2") (pin "24") (pinfunction "~{OE}_24") (pintype "input"))
      (node (ref "IC3") (pin "11") (pinfunction "GND_11") (pintype "power_in"))
      (node (ref "IC3") (pin "31") (pinfunction "GND_31") (pintype "power_in"))
      (node (ref "IC4") (pin "1") (pinfunction "VIN_1") (pintype "input"))
      (node (ref "IC5") (pin "10") (pinfunction "GND_10") (pintype "power_in"))
      (node (ref "IC6") (pin "3") (pinfunction "3_3") (pintype "passive"))
      (node (ref "IC6") (pin "4") (pinfunction "4_4") (pintype "passive"))
      (node (ref "JP2") (pin "2") (pinfunction "2_2") (pintype "passive"))
      (node (ref "JP3") (pin "5") (pinfunction "5_5") (pintype "passive"))
      (node (ref "JP4") (pin "1") (pinfunction "1_1") (pintype "passive"))
      (node (ref "JP5") (pin "1") (pinfunction "1_1") (pintype "passive"))
      (node (ref "PAD10") (pin "1") (pinfunction "P_1") (pintype "passive"))
      (node (ref "PAD13") (pin "1") (pinfunction "P_1") (pintype "passive"))
      (node (ref "PAD14") (pin "1") (pinfunction "P_1") (pintype "passive"))
      (node (ref "PAD21") (pin "1") (pinfunction "P_1") (pintype "passive"))
      (node (ref "PAD22") (pin "1") (pinfunction "P_1") (pintype "passive"))
      (node (ref "PAD5") (pin "1") (pinfunction "P_1") (pintype "passive"))
      (node (ref "PAD8") (pin "1") (pinfunction "P_1") (pintype "passive"))
      (node (ref "PAD9") (pin "1") (pinfunction "P_1") (pintype "passive"))
      (node (ref "R1") (pin "1") (pinfunction "1_1") (pintype "passive"))
      (node (ref "R2") (pin "1") (pinfunction "1_1") (pintype "passive"))
      (node (ref "R3") (pin "1") (pinfunction "1_1") (pintype "passive"))
      (node (ref "SW1") (pin "1") (pinfunction "1_1") (pintype "passive"))
      (node (ref "SW1") (pin "2") (pinfunction "2_2") (pintype "passive"))
      (node (ref "U$1") (pin "10") (pinfunction "P$10_10") (pintype "bidirectional"))
      (node (ref "U$1") (pin "22") (pinfunction "P$22_22") (pintype "bidirectional"))
      (node (ref "U$1") (pin "30") (pinfunction "P$30_30") (pintype "bidirectional"))
      (node (ref "U$1") (pin "42") (pinfunction "P$42_42") (pintype "bidirectional"))
      (node (ref "U$2") (pin "P$1") (pinfunction "GND_P$1") (pintype "power_in"))
      (node (ref "U$2") (pin "P$22") (pinfunction "GND_P$22") (pintype "power_in"))
      (node (ref "U$2") (pin "P$23") (pinfunction "GND_P$23") (pintype "power_in"))
      (node (ref "U$2") (pin "P$44") (pinfunction "GND_P$44") (pintype "power_in"))
      (node (ref "U$3") (pin "P$2") (pinfunction "P$2_P$2") (pintype "power_in"))
    )
    (net (code "70") (name "Net-(C11-Pad1)") (class "Default")
      (node (ref "C11") (pin "1") (pinfunction "1_1") (pintype "passive"))
      (node (ref "D1") (pin "C") (pinfunction "C_C") (pintype "passive"))
      (node (ref "D2") (pin "C") (pinfunction "C_C") (pintype "passive"))
      (node (ref "IC6") (pin "8") (pinfunction "8_8") (pintype "passive"))
    )
    (net (code "71") (name "Net-(C11-Pad2)") (class "Default")
      (node (ref "C11") (pin "2") (pinfunction "2_2") (pintype "passive"))
      (node (ref "IC6") (pin "1") (pinfunction "1_1") (pintype "passive"))
      (node (ref "Q2") (pin "2") (pinfunction "2_2") (pintype "passive"))
    )
    (net (code "72") (name "Net-(D2-PadA)") (class "Default")
      (node (ref "D2") (pin "A") (pinfunction "A_A") (pintype "passive"))
      (node (ref "U$3") (pin "P$1") (pinfunction "P$1_P$1") (pintype "power_in"))
    )
    (net (code "73") (name "Net-(IC3-(ADC2)PA2)") (class "Default")
      (node (ref "IC3") (pin "38") (pinfunction "(ADC2)PA2_38") (pintype "bidirectional"))
      (node (ref "SW1") (pin "8") (pinfunction "8_8") (pintype "passive"))
    )
    (net (code "74") (name "Net-(IC3-(ADC3)PA3)") (class "Default")
      (node (ref "IC3") (pin "37") (pinfunction "(ADC3)PA3_37") (pintype "bidirectional"))
      (node (ref "SW1") (pin "7") (pinfunction "7_7") (pintype "passive"))
    )
    (net (code "75") (name "Net-(IC3-(ADC4)PA4)") (class "Default")
      (node (ref "IC3") (pin "36") (pinfunction "(ADC4)PA4_36") (pintype "bidirectional"))
      (node (ref "JP4") (pin "2") (pinfunction "2_2") (pintype "passive"))
    )
    (net (code "76") (name "Net-(IC3-(ADC5)PA5)") (class "Default")
      (node (ref "IC3") (pin "35") (pinfunction "(ADC5)PA5_35") (pintype "bidirectional"))
      (node (ref "JP5") (pin "2") (pinfunction "2_2") (pintype "passive"))
    )
    (net (code "77") (name "Net-(IC3-(MOSI)PB5)") (class "Default")
      (node (ref "IC3") (pin "6") (pinfunction "(MOSI)PB5_6") (pintype "bidirectional"))
      (node (ref "R5") (pin "2") (pinfunction "2_2") (pintype "passive"))
    )
    (net (code "78") (name "Net-(IC3-(SCK)PB7)") (class "Default")
      (node (ref "IC3") (pin "8") (pinfunction "(SCK)PB7_8") (pintype "bidirectional"))
      (node (ref "R4") (pin "2") (pinfunction "2_2") (pintype "passive"))
    )
    (net (code "79") (name "Net-(IC3-(SS)PB4)") (class "Default")
      (node (ref "IC3") (pin "5") (pinfunction "(SS)PB4_5") (pintype "bidirectional"))
      (node (ref "R6") (pin "2") (pinfunction "2_2") (pintype "passive"))
    )
    (net (code "80") (name "Net-(IC3-(TDI)PC5)") (class "Default")
      (node (ref "IC3") (pin "27") (pinfunction "(TDI)PC5_27") (pintype "bidirectional"))
      (node (ref "IC6") (pin "5") (pinfunction "5_5") (pintype "passive"))
      (node (ref "JP3") (pin "4") (pinfunction "4_4") (pintype "passive"))
      (node (ref "R8") (pin "1") (pinfunction "1_1") (pintype "passive"))
    )
    (net (code "81") (name "Net-(IC3-(TOSC1)PC6)") (class "Default")
      (node (ref "IC3") (pin "28") (pinfunction "(TOSC1)PC6_28") (pintype "bidirectional"))
      (node (ref "IC6") (pin "6") (pinfunction "6_6") (pintype "passive"))
      (node (ref "JP3") (pin "3") (pinfunction "3_3") (pintype "passive"))
      (node (ref "R9") (pin "1") (pinfunction "1_1") (pintype "passive"))
    )
    (net (code "82") (name "Net-(IC3-(TOSC2)PC7)") (class "Default")
      (node (ref "IC3") (pin "29") (pinfunction "(TOSC2)PC7_29") (pintype "bidirectional"))
      (node (ref "JP3") (pin "2") (pinfunction "2_2") (pintype "passive"))
    )
    (net (code "83") (name "Net-(IC3-RESET)") (class "Default")
      (node (ref "IC3") (pin "9") (pinfunction "RESET_9") (pintype "input"))
      (node (ref "R7") (pin "1") (pinfunction "1_1") (pintype "passive"))
      (node (ref "SW1") (pin "4") (pinfunction "4_4") (pintype "passive"))
    )
    (net (code "84") (name "Net-(IC3-XTAL1)") (class "Default")
      (node (ref "C6") (pin "1") (pinfunction "1_1") (pintype "passive"))
      (node (ref "IC3") (pin "13") (pinfunction "XTAL1_13") (pintype "bidirectional"))
      (node (ref "Q1") (pin "1") (pinfunction "1_1") (pintype "passive"))
    )
    (net (code "85") (name "Net-(IC3-XTAL2)") (class "Default")
      (node (ref "C7") (pin "1") (pinfunction "1_1") (pintype "passive"))
      (node (ref "IC3") (pin "12") (pinfunction "XTAL2_12") (pintype "bidirectional"))
      (node (ref "Q1") (pin "2") (pinfunction "2_2") (pintype "passive"))
    )
    (net (code "86") (name "Net-(IC6-Pad2)") (class "Default")
      (node (ref "IC6") (pin "2") (pinfunction "2_2") (pintype "passive"))
      (node (ref "Q2") (pin "1") (pinfunction "1_1") (pintype "passive"))
    )
    (net (code "87") (name "Net-(IC6-Pad7)") (class "Default")
      (node (ref "IC6") (pin "7") (pinfunction "7_7") (pintype "passive"))
      (node (ref "JP2") (pin "1") (pinfunction "1_1") (pintype "passive"))
    )
    (net (code "88") (name "Net-(LED_G-PadA)") (class "Default")
      (node (ref "LED_G") (pin "A") (pinfunction "A_A") (pintype "passive"))
      (node (ref "R11") (pin "2") (pinfunction "2_2") (pintype "passive"))
    )
    (net (code "89") (name "Net-(LED_R-PadA)") (class "Default")
      (node (ref "LED_R") (pin "A") (pinfunction "A_A") (pintype "passive"))
      (node (ref "R10") (pin "2") (pinfunction "2_2") (pintype "passive"))
    )
    (net (code "90") (name "VCCINT") (class "Default")
      (node (ref "C1") (pin "1") (pinfunction "1_1") (pintype "passive"))
      (node (ref "C4") (pin "1") (pinfunction "1_1") (pintype "passive"))
      (node (ref "JP1") (pin "2") (pinfunction "2_2") (pintype "passive"))
      (node (ref "U$1") (pin "15") (pinfunction "P$15_15") (pintype "bidirectional"))
      (node (ref "U$1") (pin "23") (pinfunction "P$23_23") (pintype "bidirectional"))
      (node (ref "U$1") (pin "3") (pinfunction "P$3_3") (pintype "bidirectional"))
      (node (ref "U$1") (pin "35") (pinfunction "P$35_35") (pintype "bidirectional"))
    )
    (net (code "91") (name "unconnected-(IC3-(ADC6)PA6-Pad34)") (class "Default")
      (node (ref "IC3") (pin "34") (pinfunction "(ADC6)PA6_34") (pintype "bidirectional"))
    )
    (net (code "92") (name "unconnected-(IC3-(ADC7)PA7-Pad33)") (class "Default")
      (node (ref "IC3") (pin "33") (pinfunction "(ADC7)PA7_33") (pintype "bidirectional"))
    )
    (net (code "93") (name "unconnected-(IC3-(AIN0{slash}INT2)PB2-Pad3)") (class "Default")
      (node (ref "IC3") (pin "3") (pinfunction "(AIN0/INT2)PB2_3") (pintype "bidirectional"))
    )
    (net (code "94") (name "unconnected-(IC3-(AIN1{slash}OC0)PB3-Pad4)") (class "Default")
      (node (ref "IC3") (pin "4") (pinfunction "(AIN1/OC0)PB3_4") (pintype "bidirectional"))
    )
    (net (code "95") (name "unconnected-(IC3-(INT1)PD3-Pad17)") (class "Default")
      (node (ref "IC3") (pin "17") (pinfunction "(INT1)PD3_17") (pintype "bidirectional"))
    )
    (net (code "96") (name "unconnected-(IC3-(OC1A)PD5-Pad19)") (class "Default")
      (node (ref "IC3") (pin "19") (pinfunction "(OC1A)PD5_19") (pintype "bidirectional"))
    )
    (net (code "97") (name "unconnected-(IC3-(OC1B)PD4-Pad18)") (class "Default")
      (node (ref "IC3") (pin "18") (pinfunction "(OC1B)PD4_18") (pintype "bidirectional"))
    )
    (net (code "98") (name "unconnected-(IC3-(OC2)PD7-Pad21)") (class "Default")
      (node (ref "IC3") (pin "21") (pinfunction "(OC2)PD7_21") (pintype "bidirectional"))
    )
    (net (code "99") (name "unconnected-(IC3-(RXD)PD0-Pad14)") (class "Default")
      (node (ref "IC3") (pin "14") (pinfunction "(RXD)PD0_14") (pintype "bidirectional"))
    )
    (net (code "100") (name "unconnected-(IC3-(T0{slash}XCK)PB0-Pad1)") (class "Default")
      (node (ref "IC3") (pin "1") (pinfunction "(T0/XCK)PB0_1") (pintype "bidirectional"))
    )
    (net (code "101") (name "unconnected-(IC3-(T1)PB1-Pad2)") (class "Default")
      (node (ref "IC3") (pin "2") (pinfunction "(T1)PB1_2") (pintype "bidirectional"))
    )
    (net (code "102") (name "unconnected-(IC3-(TDO)PC4-Pad26)") (class "Default")
      (node (ref "IC3") (pin "26") (pinfunction "(TDO)PC4_26") (pintype "bidirectional"))
    )
    (net (code "103") (name "unconnected-(IC3-(TMS)PC3-Pad25)") (class "Default")
      (node (ref "IC3") (pin "25") (pinfunction "(TMS)PC3_25") (pintype "bidirectional"))
    )
    (net (code "104") (name "unconnected-(IC3-(TXD)PD1-Pad15)") (class "Default")
      (node (ref "IC3") (pin "15") (pinfunction "(TXD)PD1_15") (pintype "bidirectional"))
    )
    (net (code "105") (name "unconnected-(IC3-AREF-Pad32)") (class "Default")
      (node (ref "IC3") (pin "32") (pinfunction "AREF_32") (pintype "passive"))
    )
    (net (code "106") (name "unconnected-(PAD1-P-Pad1)") (class "Default")
      (node (ref "PAD1") (pin "1") (pinfunction "P_1") (pintype "passive"))
    )
    (net (code "107") (name "unconnected-(PAD3-P-Pad1)") (class "Default")
      (node (ref "PAD3") (pin "1") (pinfunction "P_1") (pintype "passive"))
    )
    (net (code "108") (name "unconnected-(U$1-P$2-Pad2)") (class "Default")
      (node (ref "U$1") (pin "2") (pinfunction "P$2_2") (pintype "bidirectional"))
    )
    (net (code "109") (name "unconnected-(U$1-P$5-Pad5)") (class "Default")
      (node (ref "U$1") (pin "5") (pinfunction "P$5_5") (pintype "bidirectional"))
    )
    (net (code "110") (name "unconnected-(U$1-P$40-Pad40)") (class "Default")
      (node (ref "U$1") (pin "40") (pinfunction "P$40_40") (pintype "bidirectional"))
    )
    (net (code "111") (name "unconnected-(U$1-P$44-Pad44)") (class "Default")
      (node (ref "U$1") (pin "44") (pinfunction "P$44_44") (pintype "bidirectional"))
    )
    (net (code "112") (name "unconnected-(U$2-CA13-PadP$30)") (class "Default")
      (node (ref "U$2") (pin "P$30") (pinfunction "CA13_P$30") (pintype "bidirectional"))
    )
    (net (code "113") (name "unconnected-(U$2-IO2-PadP$29)") (class "Default")
      (node (ref "U$2") (pin "P$29") (pinfunction "IO2_P$29") (pintype "bidirectional"))
    )
    (net (code "114") (name "unconnected-(U$2-VR{slash}W-PadP$6)") (class "Default")
      (node (ref "U$2") (pin "P$6") (pinfunction "VR/W_P$6") (pintype "bidirectional"))
    )
    (net (code "115") (name "unconnected-(U$2-~{IRQ}-PadP$4)") (class "Default")
      (node (ref "U$2") (pin "P$4") (pinfunction "~{IRQ}_P$4") (pintype "bidirectional"))
    )
    (net (code "116") (name "unconnected-(U$2-~{NMI}-PadP$26)") (class "Default")
      (node (ref "U$2") (pin "P$26") (pinfunction "~{NMI}_P$26") (pintype "bidirectional"))
    )
    (net (code "117") (name "unconnected-(U$2-~{ROMH}-PadP$24)") (class "Default")
      (node (ref "U$2") (pin "P$24") (pinfunction "~{ROMH}_P$24") (pintype "bidirectional"))
    )
  )
)
